# Schematic_v2.net
KiCad netlist of a schematic drawn in EAGLE
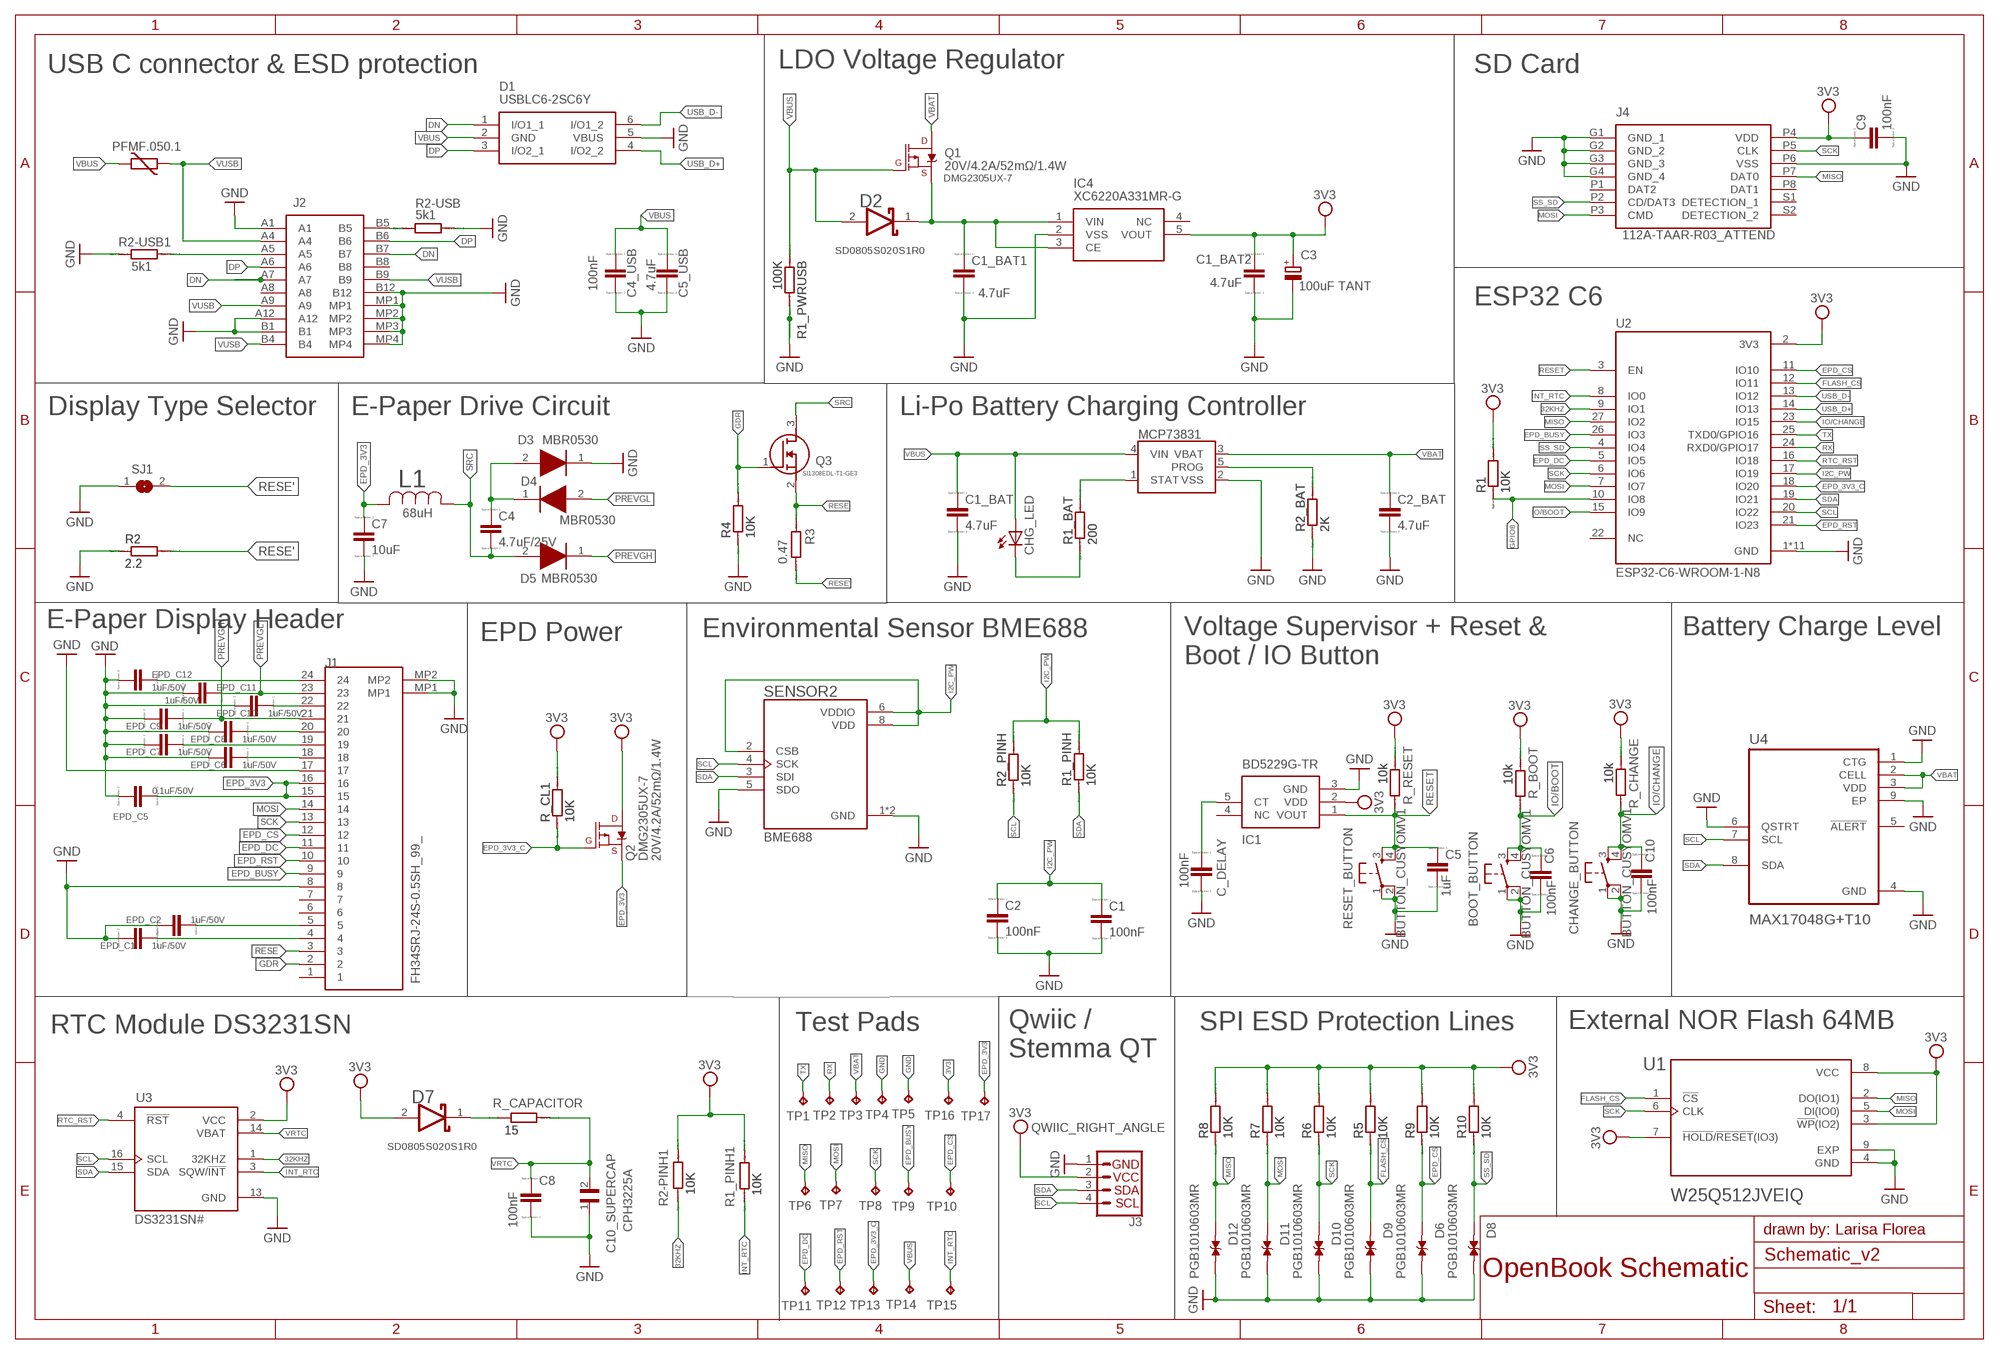
[diagram p0: schematic, sheet 1]

(export (version "E")
  (design (tool "Eeschema 10.0.6"))
  (components
    (comp (ref "BOOT_BUTTON")
      (value "BUTTON_CUSYOMV1")
      (footprint "eagle-import:MYBUTTON")
      (libsource (lib "eagle-import") (part "BUTTON_CUSYOMV1"))
    )
    (comp (ref "C1")
      (value "100nF")
      (footprint "eagle-import:EAGLE-LTSPICE_C0402")
      (libsource (lib "eagle-import") (part "EAGLE-LTSPICE_CC0402"))
    )
    (comp (ref "C1_BAT")
      (value "4.7uF")
      (footprint "eagle-import:EAGLE-LTSPICE_C0402")
      (libsource (lib "eagle-import") (part "EAGLE-LTSPICE_CC0402"))
    )
    (comp (ref "C1_BAT1")
      (value "4.7uF")
      (footprint "eagle-import:ESP32_WROVER_EAGLE-LTSPICE_C0402")
      (libsource (lib "eagle-import") (part "ESP32_WROVER_EAGLE-LTSPICE_CC0402"))
    )
    (comp (ref "C1_BAT2")
      (value "4.7uF")
      (footprint "eagle-import:ESP32_WROVER_EAGLE-LTSPICE_C0402")
      (libsource (lib "eagle-import") (part "ESP32_WROVER_EAGLE-LTSPICE_CC0402"))
    )
    (comp (ref "C2")
      (value "100nF")
      (footprint "eagle-import:EAGLE-LTSPICE_C0402")
      (libsource (lib "eagle-import") (part "EAGLE-LTSPICE_CC0402"))
    )
    (comp (ref "C2_BAT")
      (value "4.7uF")
      (footprint "eagle-import:EAGLE-LTSPICE_C0402")
      (libsource (lib "eagle-import") (part "EAGLE-LTSPICE_CC0402"))
    )
    (comp (ref "C3")
      (value "100uF TANT")
      (footprint "eagle-import:RCL_CT3528")
      (libsource (lib "eagle-import") (part "RCL_CPOL-EUCT3528"))
    )
    (comp (ref "C4")
      (value "4.7uF/25V")
      (footprint "eagle-import:ESP32_WROVER_EAGLE-LTSPICE_C0402")
      (libsource (lib "eagle-import") (part "ESP32_WROVER_EAGLE-LTSPICE_CC0402"))
    )
    (comp (ref "C4_USB")
      (value "100nF")
      (footprint "eagle-import:ESP32_WROVER_EAGLE-LTSPICE_C0402")
      (libsource (lib "eagle-import") (part "ESP32_WROVER_EAGLE-LTSPICE_CC0402"))
    )
    (comp (ref "C5")
      (value "1uF")
      (footprint "eagle-import:EAGLE-LTSPICE_C0402")
      (libsource (lib "eagle-import") (part "EAGLE-LTSPICE_CC0402"))
    )
    (comp (ref "C5_USB")
      (value "4.7uF")
      (footprint "eagle-import:ESP32_WROVER_EAGLE-LTSPICE_C0402")
      (libsource (lib "eagle-import") (part "ESP32_WROVER_EAGLE-LTSPICE_CC0402"))
    )
    (comp (ref "C6")
      (value "100nF")
      (footprint "eagle-import:EAGLE-LTSPICE_C0402")
      (libsource (lib "eagle-import") (part "EAGLE-LTSPICE_CC0402"))
    )
    (comp (ref "C7")
      (value "10uF")
      (footprint "eagle-import:ESP32_WROVER_EAGLE-LTSPICE_C0402")
      (libsource (lib "eagle-import") (part "ESP32_WROVER_EAGLE-LTSPICE_CC0402"))
    )
    (comp (ref "C8")
      (value "100nF")
      (footprint "eagle-import:EAGLE-LTSPICE_C0402")
      (libsource (lib "eagle-import") (part "EAGLE-LTSPICE_CC0402"))
    )
    (comp (ref "C9")
      (value "100nF")
      (footprint "eagle-import:EAGLE-LTSPICE_C0402")
      (libsource (lib "eagle-import") (part "EAGLE-LTSPICE_CC0402"))
    )
    (comp (ref "C10")
      (value "100nF")
      (footprint "eagle-import:EAGLE-LTSPICE_C0402")
      (libsource (lib "eagle-import") (part "EAGLE-LTSPICE_CC0402"))
    )
    (comp (ref "C10_SUPERCAP")
      (value "CPH3225A")
      (footprint "eagle-import:CAPCP3225X100N")
      (fields (field (name "MF") "Seiko Instruments"))
      (libsource (lib "eagle-import") (part "CPH3225A"))
    )
    (comp (ref "CHANGE_BUTTON")
      (value "BUTTON_CUSYOMV1")
      (footprint "eagle-import:MYBUTTON")
      (libsource (lib "eagle-import") (part "BUTTON_CUSYOMV1"))
    )
    (comp (ref "CHG_LED")
      (value "ADAFRUIT_LEDCHIP-LED0603")
      (footprint "eagle-import:ADAFRUIT_CHIP-LED0603")
      (libsource (lib "eagle-import") (part "ADAFRUIT_LEDCHIP-LED0603"))
    )
    (comp (ref "C_DELAY")
      (value "100nF")
      (footprint "eagle-import:EAGLE-LTSPICE_C0402")
      (libsource (lib "eagle-import") (part "EAGLE-LTSPICE_CC0402"))
    )
    (comp (ref "D1")
      (value "USBLC6-2SC6Y")
      (footprint "eagle-import:SOT95P280X145-6N")
      (fields (field (name "MF") "STMicroelectronics"))
      (libsource (lib "eagle-import") (part "USBLC6-2SC6Y"))
    )
    (comp (ref "D2")
      (value "ESP32_WROVER_AVX---SD0805S020S1R0_AVX_SD0805S020S1R0_0_0AVX_SD0805S020S1R0_0_0")
      (footprint "eagle-import:ESP32_WROVER_AVX---SD0805S020S1R0_AVX_SD0805S020S1R0_0")
      (fields
        (field (name "DIGIKEY_PART_NUMBER") "478-7800-1-ND")
        (field (name "MF") "AVX")
        (field (name "MOUSER_PART_NUMBER") "581-SD0805S020S1R0")
      )
      (libsource (lib "eagle-import") (part "ESP32_WROVER_AVX---SD0805S020S1R0_AVX_SD0805S020S1R0_0_0AVX_SD0805S020S1R0_0_0"))
    )
    (comp (ref "D3")
      (value "MBR0530")
      (footprint "eagle-import:SOD3716X135N")
      (fields (field (name "MF") "ON Semiconductor"))
      (libsource (lib "eagle-import") (part "MBR0530"))
    )
    (comp (ref "D4")
      (value "MBR0530")
      (footprint "eagle-import:SOD3716X135N")
      (fields (field (name "MF") "ON Semiconductor"))
      (libsource (lib "eagle-import") (part "MBR0530"))
    )
    (comp (ref "D5")
      (value "MBR0530")
      (footprint "eagle-import:SOD3716X135N")
      (fields (field (name "MF") "ON Semiconductor"))
      (libsource (lib "eagle-import") (part "MBR0530"))
    )
    (comp (ref "D6")
      (value "PGB1010603MR")
      (footprint "eagle-import:DIOC1608X36N")
      (fields (field (name "MF") "Littelfuse Inc."))
      (libsource (lib "eagle-import") (part "PGB1010603MR"))
    )
    (comp (ref "D7")
      (value "ESP32_WROVER_AVX---SD0805S020S1R0_AVX_SD0805S020S1R0_0_0AVX_SD0805S020S1R0_0_0")
      (footprint "eagle-import:ESP32_WROVER_AVX---SD0805S020S1R0_AVX_SD0805S020S1R0_0")
      (fields
        (field (name "DIGIKEY_PART_NUMBER") "478-7800-1-ND")
        (field (name "MF") "AVX")
        (field (name "MOUSER_PART_NUMBER") "581-SD0805S020S1R0")
      )
      (libsource (lib "eagle-import") (part "ESP32_WROVER_AVX---SD0805S020S1R0_AVX_SD0805S020S1R0_0_0AVX_SD0805S020S1R0_0_0"))
    )
    (comp (ref "D8")
      (value "PGB1010603MR")
      (footprint "eagle-import:DIOC1608X36N")
      (fields (field (name "MF") "Littelfuse Inc."))
      (libsource (lib "eagle-import") (part "PGB1010603MR"))
    )
    (comp (ref "D9")
      (value "PGB1010603MR")
      (footprint "eagle-import:DIOC1608X36N")
      (fields (field (name "MF") "Littelfuse Inc."))
      (libsource (lib "eagle-import") (part "PGB1010603MR"))
    )
    (comp (ref "D10")
      (value "PGB1010603MR")
      (footprint "eagle-import:DIOC1608X36N")
      (fields (field (name "MF") "Littelfuse Inc."))
      (libsource (lib "eagle-import") (part "PGB1010603MR"))
    )
    (comp (ref "D11")
      (value "PGB1010603MR")
      (footprint "eagle-import:DIOC1608X36N")
      (fields (field (name "MF") "Littelfuse Inc."))
      (libsource (lib "eagle-import") (part "PGB1010603MR"))
    )
    (comp (ref "D12")
      (value "PGB1010603MR")
      (footprint "eagle-import:DIOC1608X36N")
      (fields (field (name "MF") "Littelfuse Inc."))
      (libsource (lib "eagle-import") (part "PGB1010603MR"))
    )
    (comp (ref "EPD_C1")
      (value "1uF/50V")
      (footprint "eagle-import:ESP32_WROVER_EAGLE-LTSPICE_C0402")
      (libsource (lib "eagle-import") (part "DeskAssistant v19 v1_vf.GPlzlSHfQFaX3NeFr78fQQ_ESP32_WROVER_EAGLE-LTSPICE_CC0402"))
    )
    (comp (ref "EPD_C2")
      (value "1uF/50V")
      (footprint "eagle-import:ESP32_WROVER_EAGLE-LTSPICE_C0402")
      (libsource (lib "eagle-import") (part "DeskAssistant v19 v1_vf.GPlzlSHfQFaX3NeFr78fQQ_ESP32_WROVER_EAGLE-LTSPICE_CC0402"))
    )
    (comp (ref "EPD_C5")
      (value "0.1uF/50V")
      (footprint "eagle-import:ESP32_WROVER_EAGLE-LTSPICE_C0402")
      (libsource (lib "eagle-import") (part "DeskAssistant v19 v1_vf.GPlzlSHfQFaX3NeFr78fQQ_ESP32_WROVER_EAGLE-LTSPICE_CC0402"))
    )
    (comp (ref "EPD_C6")
      (value "1uF/50V")
      (footprint "eagle-import:ESP32_WROVER_EAGLE-LTSPICE_C0402")
      (libsource (lib "eagle-import") (part "DeskAssistant v19 v1_vf.GPlzlSHfQFaX3NeFr78fQQ_ESP32_WROVER_EAGLE-LTSPICE_CC0402"))
    )
    (comp (ref "EPD_C7")
      (value "1uF/50V")
      (footprint "eagle-import:ESP32_WROVER_EAGLE-LTSPICE_C0402")
      (libsource (lib "eagle-import") (part "DeskAssistant v19 v1_vf.GPlzlSHfQFaX3NeFr78fQQ_ESP32_WROVER_EAGLE-LTSPICE_CC0402"))
    )
    (comp (ref "EPD_C8")
      (value "1uF/50V")
      (footprint "eagle-import:ESP32_WROVER_EAGLE-LTSPICE_C0402")
      (libsource (lib "eagle-import") (part "DeskAssistant v19 v1_vf.GPlzlSHfQFaX3NeFr78fQQ_ESP32_WROVER_EAGLE-LTSPICE_CC0402"))
    )
    (comp (ref "EPD_C9")
      (value "1uF/50V")
      (footprint "eagle-import:ESP32_WROVER_EAGLE-LTSPICE_C0402")
      (libsource (lib "eagle-import") (part "DeskAssistant v19 v1_vf.GPlzlSHfQFaX3NeFr78fQQ_ESP32_WROVER_EAGLE-LTSPICE_CC0402"))
    )
    (comp (ref "EPD_C10")
      (value "1uF/50V")
      (footprint "eagle-import:ESP32_WROVER_EAGLE-LTSPICE_C0402")
      (libsource (lib "eagle-import") (part "DeskAssistant v19 v1_vf.GPlzlSHfQFaX3NeFr78fQQ_ESP32_WROVER_EAGLE-LTSPICE_CC0402"))
    )
    (comp (ref "EPD_C11")
      (value "1uF/50V")
      (footprint "eagle-import:ESP32_WROVER_EAGLE-LTSPICE_C0402")
      (libsource (lib "eagle-import") (part "DeskAssistant v19 v1_vf.GPlzlSHfQFaX3NeFr78fQQ_ESP32_WROVER_EAGLE-LTSPICE_CC0402"))
    )
    (comp (ref "EPD_C12")
      (value "1uF/50V")
      (footprint "eagle-import:ESP32_WROVER_EAGLE-LTSPICE_C0402")
      (libsource (lib "eagle-import") (part "DeskAssistant v19 v1_vf.GPlzlSHfQFaX3NeFr78fQQ_ESP32_WROVER_EAGLE-LTSPICE_CC0402"))
    )
    (comp (ref "IC1")
      (value "BD5229G-TR")
      (footprint "eagle-import:SOT95P280X125-5N")
      (fields (field (name "MOUSER_PART_NUMBER") "755-BD5229G-TR"))
      (libsource (lib "eagle-import") (part "BD5229G-TR"))
    )
    (comp (ref "IC4")
      (value "XC6220A331MR-G")
      (footprint "eagle-import:SOT95P280X120-5N")
      (fields (field (name "MOUSER_PART_NUMBER") "865-XC6220A331MR-G"))
      (libsource (lib "eagle-import") (part "XC6220A331MR-G"))
    )
    (comp (ref "J1")
      (value "FH34SRJ-24S-0.5SH_99_")
      (footprint "eagle-import:FH34SRJ24S05SH99")
      (fields
        (field (name "MANUFACTURER_PART_NUMBER") "FH34SRJ-24S-0.5SH(99)")
        (field (name "MOUSER_PART_NUMBER") "798-FH34SRJ24S05SH99")
      )
      (libsource (lib "eagle-import") (part "FH34SRJ-24S-0.5SH_99_"))
    )
    (comp (ref "J2")
      (value "SAMACSYS_PARTS_USB4110-GF-A")
      (footprint "eagle-import:SAMACSYS_PARTS_USB4110GFA")
      (fields
        (field (name "MANUFACTURER_PART_NUMBER") "USB4110-GF-A")
        (field (name "MOUSER_PART_NUMBER") "640-USB4110-GF-A")
      )
      (libsource (lib "eagle-import") (part "SAMACSYS_PARTS_USB4110-GF-A"))
    )
    (comp (ref "J3")
      (value "QWIIC_RIGHT_ANGLE")
      (footprint "eagle-import:JST04_1MM_RA")
      (libsource (lib "eagle-import") (part "QWIIC_CONNECTORJS-1MM"))
    )
    (comp (ref "J4")
      (value "112A-TAAR-R03_ATTEND")
      (footprint "eagle-import:112ATAARR03ATTEND")
      (fields (field (name "MANUFACTURER_PART_NUMBER") "112A-TAAR-R03 ATTEND"))
      (libsource (lib "eagle-import") (part "112A-TAAR-R03_ATTEND"))
    )
    (comp (ref "L1")
      (value "744043680IND_4828-WE-TPC_WRE")
      (footprint "eagle-import:IND_4828-WE-TPC_WRE")
      (fields
        (field (name "MANUFACTURER_PART_NUMBER") "744043680")
        (field (name "68UH") "68uH")
        (field (name "COPYRIGHT") "Copyright (C) 2024 Ultra Librarian. All rights reserved.")
      )
      (libsource (lib "eagle-import") (part "744043680IND_4828-WE-TPC_WRE"))
    )
    (comp (ref "MCP73831")
      (value "ESP32_WROVER_SPARKFUN-IC-POWER_MCP73831")
      (footprint "eagle-import:ESP32_WROVER_SPARKFUN-IC-POWER_SOT23-5")
      (libsource (lib "eagle-import") (part "ESP32_WROVER_SPARKFUN-IC-POWER_MCP73831"))
    )
    (comp (ref "PFMF.050.1")
      (value "ESP32C6_VARISTORCN1812")
      (footprint "eagle-import:ESP32C6_VARISTOR_CT_CN1812")
      (libsource (lib "eagle-import") (part "ESP32C6_VARISTORCN1812"))
    )
    (comp (ref "Q1")
      (value "20V/4.2A/52mΩ/1.4W")
      (footprint "eagle-import:ESP32_WROVER_SPARKFUN-DISCRETESEMI_SOT23-3")
      (libsource (lib "eagle-import") (part "ESP32_WROVER_SPARKFUN-DISCRETESEMI_MOSFET_PCH-DMG2305UX-7"))
    )
    (comp (ref "Q2")
      (value "20V/4.2A/52mΩ/1.4W")
      (footprint "eagle-import:ESP32_WROVER_SPARKFUN-DISCRETESEMI_SOT23-3")
      (libsource (lib "eagle-import") (part "ESP32_WROVER_SPARKFUN-DISCRETESEMI_MOSFET_PCH-DMG2305UX-7"))
    )
    (comp (ref "Q3")
      (value "SI1308EDL-T1-GE3")
      (footprint "eagle-import:SOT65P210X110-3N")
      (fields (field (name "MF") "Vishay Siliconix"))
      (libsource (lib "eagle-import") (part "SI1308EDL-T1-GE3"))
    )
    (comp (ref "R1")
      (value "10K")
      (footprint "eagle-import:ESP32_WROVER_EAGLE-LTSPICE_R0402")
      (libsource (lib "eagle-import") (part "ESP32_WROVER_EAGLE-LTSPICE_RR0402"))
    )
    (comp (ref "R1_BAT")
      (value "200")
      (footprint "eagle-import:ESP32_WROVER_EAGLE-LTSPICE_R0402")
      (libsource (lib "eagle-import") (part "ESP32_WROVER_EAGLE-LTSPICE_RR0402"))
    )
    (comp (ref "R1_PINH")
      (value "10K")
      (footprint "eagle-import:ESP32_WROVER_EAGLE-LTSPICE_R0402")
      (libsource (lib "eagle-import") (part "ESP32_WROVER_EAGLE-LTSPICE_RR0402"))
    )
    (comp (ref "R1_PINH1")
      (value "10K")
      (footprint "eagle-import:ESP32_WROVER_EAGLE-LTSPICE_R0402")
      (libsource (lib "eagle-import") (part "ESP32_WROVER_EAGLE-LTSPICE_RR0402"))
    )
    (comp (ref "R1_PWRUSB")
      (value "100K")
      (footprint "eagle-import:ESP32_WROVER_EAGLE-LTSPICE_R0402")
      (libsource (lib "eagle-import") (part "ESP32_WROVER_EAGLE-LTSPICE_RR0402"))
    )
    (comp (ref "R2")
      (value "2.2")
      (footprint "eagle-import:ESP32_WROVER_EAGLE-LTSPICE_R0402")
      (libsource (lib "eagle-import") (part "ESP32_WROVER_EAGLE-LTSPICE_RR0402"))
    )
    (comp (ref "R2-PINH1")
      (value "10K")
      (footprint "eagle-import:ESP32_WROVER_EAGLE-LTSPICE_R0402")
      (libsource (lib "eagle-import") (part "ESP32_WROVER_EAGLE-LTSPICE_RR0402"))
    )
    (comp (ref "R2-USB")
      (value "5k1")
      (footprint "eagle-import:ESP32_WROVER_EAGLE-LTSPICE_R0402")
      (libsource (lib "eagle-import") (part "ESP32_WROVER_EAGLE-LTSPICE_RR0402"))
    )
    (comp (ref "R2-USB1")
      (value "5k1")
      (footprint "eagle-import:ESP32_WROVER_EAGLE-LTSPICE_R0402")
      (libsource (lib "eagle-import") (part "ESP32_WROVER_EAGLE-LTSPICE_RR0402"))
    )
    (comp (ref "R2_BAT")
      (value "2K")
      (footprint "eagle-import:ESP32_WROVER_EAGLE-LTSPICE_R0402")
      (libsource (lib "eagle-import") (part "ESP32_WROVER_EAGLE-LTSPICE_RR0402"))
    )
    (comp (ref "R2_PINH")
      (value "10K")
      (footprint "eagle-import:ESP32_WROVER_EAGLE-LTSPICE_R0402")
      (libsource (lib "eagle-import") (part "ESP32_WROVER_EAGLE-LTSPICE_RR0402"))
    )
    (comp (ref "R3")
      (value "0.47")
      (footprint "eagle-import:ESP32_WROVER_EAGLE-LTSPICE_R0402")
      (libsource (lib "eagle-import") (part "ESP32_WROVER_EAGLE-LTSPICE_RR0402"))
    )
    (comp (ref "R4")
      (value "10K")
      (footprint "eagle-import:ESP32_WROVER_EAGLE-LTSPICE_R0402")
      (libsource (lib "eagle-import") (part "ESP32_WROVER_EAGLE-LTSPICE_RR0402"))
    )
    (comp (ref "R5")
      (value "10K")
      (footprint "eagle-import:ESP32_WROVER_EAGLE-LTSPICE_R0402")
      (libsource (lib "eagle-import") (part "DeskAssistant v19 v1_vf.GPlzlSHfQFaX3NeFr78fQQ_ESP32_WROVER_EAGLE-LTSPICE_RR0402"))
    )
    (comp (ref "R6")
      (value "10K")
      (footprint "eagle-import:ESP32_WROVER_EAGLE-LTSPICE_R0402")
      (libsource (lib "eagle-import") (part "DeskAssistant v19 v1_vf.GPlzlSHfQFaX3NeFr78fQQ_ESP32_WROVER_EAGLE-LTSPICE_RR0402"))
    )
    (comp (ref "R7")
      (value "10K")
      (footprint "eagle-import:ESP32_WROVER_EAGLE-LTSPICE_R0402")
      (libsource (lib "eagle-import") (part "DeskAssistant v19 v1_vf.GPlzlSHfQFaX3NeFr78fQQ_ESP32_WROVER_EAGLE-LTSPICE_RR0402"))
    )
    (comp (ref "R8")
      (value "10K")
      (footprint "eagle-import:ESP32_WROVER_EAGLE-LTSPICE_R0402")
      (libsource (lib "eagle-import") (part "DeskAssistant v19 v1_vf.GPlzlSHfQFaX3NeFr78fQQ_ESP32_WROVER_EAGLE-LTSPICE_RR0402"))
    )
    (comp (ref "R9")
      (value "10K")
      (footprint "eagle-import:ESP32_WROVER_EAGLE-LTSPICE_R0402")
      (libsource (lib "eagle-import") (part "DeskAssistant v19 v1_vf.GPlzlSHfQFaX3NeFr78fQQ_ESP32_WROVER_EAGLE-LTSPICE_RR0402"))
    )
    (comp (ref "R10")
      (value "10K")
      (footprint "eagle-import:ESP32_WROVER_EAGLE-LTSPICE_R0402")
      (libsource (lib "eagle-import") (part "DeskAssistant v19 v1_vf.GPlzlSHfQFaX3NeFr78fQQ_ESP32_WROVER_EAGLE-LTSPICE_RR0402"))
    )
    (comp (ref "RESET_BUTTON")
      (value "BUTTON_CUSYOMV1")
      (footprint "eagle-import:MYBUTTON")
      (libsource (lib "eagle-import") (part "BUTTON_CUSYOMV1"))
    )
    (comp (ref "R_BOOT")
      (value "10k")
      (footprint "eagle-import:ESP32_WROVER_EAGLE-LTSPICE_R0402")
      (libsource (lib "eagle-import") (part "ESP32_WROVER_EAGLE-LTSPICE_RR0402"))
    )
    (comp (ref "R_CAPACITOR")
      (value "15")
      (footprint "eagle-import:ESP32_WROVER_EAGLE-LTSPICE_R0402")
      (libsource (lib "eagle-import") (part "ESP32_WROVER_EAGLE-LTSPICE_RR0402"))
    )
    (comp (ref "R_CHANGE")
      (value "10k")
      (footprint "eagle-import:ESP32_WROVER_EAGLE-LTSPICE_R0402")
      (libsource (lib "eagle-import") (part "ESP32_WROVER_EAGLE-LTSPICE_RR0402"))
    )
    (comp (ref "R_CL1")
      (value "10K")
      (footprint "eagle-import:ESP32_WROVER_EAGLE-LTSPICE_R0402")
      (libsource (lib "eagle-import") (part "ESP32_WROVER_EAGLE-LTSPICE_RR0402"))
    )
    (comp (ref "R_RESET")
      (value "10k")
      (footprint "eagle-import:ESP32_WROVER_EAGLE-LTSPICE_R0402")
      (libsource (lib "eagle-import") (part "ESP32_WROVER_EAGLE-LTSPICE_RR0402"))
    )
    (comp (ref "SENSOR2")
      (value "ESP32_WROVER_BME680_BME680")
      (footprint "eagle-import:ESP32_WROVER_BME680_PSON80P300X300X100-8N")
      (fields (field (name "MF") "Bosch Sensortec") (field (name "MP") "BME680"))
      (libsource (lib "eagle-import") (part "ESP32_WROVER_BME680_BME680"))
    )
    (comp (ref "SJ1") (value "SJ") (footprint "eagle-import:SJ") (libsource (lib "eagle-import") (part "SJ")))
    (comp (ref "TP1")
      (value "TPTP20R")
      (footprint "eagle-import:TP20R")
      (libsource (lib "eagle-import") (part "TPTP20R"))
    )
    (comp (ref "TP2")
      (value "TPTP20R")
      (footprint "eagle-import:TP20R")
      (libsource (lib "eagle-import") (part "TPTP20R"))
    )
    (comp (ref "TP3")
      (value "TPTP20R")
      (footprint "eagle-import:TP20R")
      (libsource (lib "eagle-import") (part "TPTP20R"))
    )
    (comp (ref "TP4")
      (value "TPTP20R")
      (footprint "eagle-import:TP20R")
      (libsource (lib "eagle-import") (part "TPTP20R"))
    )
    (comp (ref "TP5")
      (value "TPTP20R")
      (footprint "eagle-import:TP20R")
      (libsource (lib "eagle-import") (part "TPTP20R"))
    )
    (comp (ref "TP6")
      (value "TPTP20R")
      (footprint "eagle-import:TP20R")
      (libsource (lib "eagle-import") (part "TPTP20R"))
    )
    (comp (ref "TP7")
      (value "TPTP20R")
      (footprint "eagle-import:TP20R")
      (libsource (lib "eagle-import") (part "TPTP20R"))
    )
    (comp (ref "TP8")
      (value "TPTP20R")
      (footprint "eagle-import:TP20R")
      (libsource (lib "eagle-import") (part "TPTP20R"))
    )
    (comp (ref "TP9")
      (value "TPTP20R")
      (footprint "eagle-import:TP20R")
      (libsource (lib "eagle-import") (part "TPTP20R"))
    )
    (comp (ref "TP10")
      (value "TPTP20R")
      (footprint "eagle-import:TP20R")
      (libsource (lib "eagle-import") (part "TPTP20R"))
    )
    (comp (ref "TP11")
      (value "TPTP20R")
      (footprint "eagle-import:TP20R")
      (libsource (lib "eagle-import") (part "TPTP20R"))
    )
    (comp (ref "TP12")
      (value "TPTP20R")
      (footprint "eagle-import:TP20R")
      (libsource (lib "eagle-import") (part "TPTP20R"))
    )
    (comp (ref "TP13")
      (value "TPTP20R")
      (footprint "eagle-import:TP20R")
      (libsource (lib "eagle-import") (part "TPTP20R"))
    )
    (comp (ref "TP14")
      (value "TPTP20R")
      (footprint "eagle-import:TP20R")
      (libsource (lib "eagle-import") (part "TPTP20R"))
    )
    (comp (ref "TP15")
      (value "TPTP20R")
      (footprint "eagle-import:TP20R")
      (libsource (lib "eagle-import") (part "TPTP20R"))
    )
    (comp (ref "TP16")
      (value "TPTP20R")
      (footprint "eagle-import:TP20R")
      (libsource (lib "eagle-import") (part "TPTP20R"))
    )
    (comp (ref "TP17")
      (value "TPTP20R")
      (footprint "eagle-import:TP20R")
      (libsource (lib "eagle-import") (part "TPTP20R"))
    )
    (comp (ref "U1")
      (value "W25Q512JVEIQ")
      (footprint "eagle-import:SON127P600X800X80-9N")
      (fields (field (name "MF") "Winbond Electronics"))
      (libsource (lib "eagle-import") (part "W25Q512JVEIQ"))
    )
    (comp (ref "U2")
      (value "ESP32-C6-WROOM-1-N8")
      (footprint "eagle-import:XCVR_ESP32-C6-WROOM-1-N8")
      (fields (field (name "MF") "Espressif Systems"))
      (libsource (lib "eagle-import") (part "ESP32-C6-WROOM-1-N8"))
    )
    (comp (ref "U3")
      (value "DS3231SN#")
      (footprint "eagle-import:SOIC127P1032X265-16N")
      (fields (field (name "MF") "Analog Devices"))
      (libsource (lib "eagle-import") (part "DS3231SN#"))
    )
    (comp (ref "U4")
      (value "MAX17048G+T10")
      (footprint "eagle-import:SON50P200X200X80-9N")
      (fields (field (name "MF") "Analog Devices"))
      (libsource (lib "eagle-import") (part "MAX17048G+T10"))
    )
  )
  (nets
    (net (code "1") (name "3V3") (class "Default")
      (node (ref "C1_BAT2") (pin "1") (pinfunction "1_1") (pintype "passive"))
      (node (ref "C3") (pin "+") (pinfunction "+_+") (pintype "passive"))
      (node (ref "C9") (pin "1") (pinfunction "1_1") (pintype "passive"))
      (node (ref "D7") (pin "2") (pinfunction "ANODE_2") (pintype "bidirectional"))
      (node (ref "IC1") (pin "2") (pinfunction "VDD_2") (pintype "bidirectional"))
      (node (ref "IC4") (pin "5") (pinfunction "VOUT_5") (pintype "bidirectional"))
      (node (ref "J3") (pin "2") (pinfunction "2_2") (pintype "power_in"))
      (node (ref "J4") (pin "P4") (pinfunction "VDD_P4") (pintype "bidirectional"))
      (node (ref "Q2") (pin "3") (pinfunction "D_3") (pintype "bidirectional"))
      (node (ref "R1") (pin "2") (pinfunction "2_2") (pintype "passive"))
      (node (ref "R10") (pin "2") (pinfunction "2_2") (pintype "passive"))
      (node (ref "R1_PINH1") (pin "2") (pinfunction "2_2") (pintype "passive"))
      (node (ref "R2-PINH1") (pin "2") (pinfunction "2_2") (pintype "passive"))
      (node (ref "R5") (pin "2") (pinfunction "2_2") (pintype "passive"))
      (node (ref "R6") (pin "2") (pinfunction "2_2") (pintype "passive"))
      (node (ref "R7") (pin "2") (pinfunction "2_2") (pintype "passive"))
      (node (ref "R8") (pin "2") (pinfunction "2_2") (pintype "passive"))
      (node (ref "R9") (pin "2") (pinfunction "2_2") (pintype "passive"))
      (node (ref "R_BOOT") (pin "1") (pinfunction "1_1") (pintype "passive"))
      (node (ref "R_CHANGE") (pin "1") (pinfunction "1_1") (pintype "passive"))
      (node (ref "R_CL1") (pin "2") (pinfunction "2_2") (pintype "passive"))
      (node (ref "R_RESET") (pin "1") (pinfunction "1_1") (pintype "passive"))
      (node (ref "TP16") (pin "TP") (pinfunction "TP_TP") (pintype "input"))
      (node (ref "U1") (pin "3") (pinfunction "~{WP}(IO2)_3") (pintype "bidirectional"))
      (node (ref "U1") (pin "7") (pinfunction "~{HOLD}/~{RESET}(IO3)_7") (pintype "bidirectional"))
      (node (ref "U1") (pin "8") (pinfunction "VCC_8") (pintype "power_in"))
      (node (ref "U2") (pin "2") (pinfunction "3V3_2") (pintype "power_in"))
      (node (ref "U3") (pin "2") (pinfunction "VCC_2") (pintype "power_in"))
    )
    (net (code "2") (name "32KHZ") (class "Default")
      (node (ref "R2-PINH1") (pin "1") (pinfunction "1_1") (pintype "passive"))
      (node (ref "U2") (pin "9") (pinfunction "IO1_9") (pintype "bidirectional"))
      (node (ref "U3") (pin "1") (pinfunction "32KHZ_1") (pintype "output"))
    )
    (net (code "3") (name "DN") (class "Default")
      (node (ref "D1") (pin "1") (pinfunction "I/O1_1_1") (pintype "bidirectional"))
      (node (ref "J2") (pin "A7") (pinfunction "A7_A7") (pintype "bidirectional"))
      (node (ref "J2") (pin "B7") (pinfunction "B7_B7") (pintype "bidirectional"))
    )
    (net (code "4") (name "DP") (class "Default")
      (node (ref "D1") (pin "3") (pinfunction "I/O2_1_3") (pintype "bidirectional"))
      (node (ref "J2") (pin "A6") (pinfunction "A6_A6") (pintype "bidirectional"))
      (node (ref "J2") (pin "B6") (pinfunction "B6_B6") (pintype "bidirectional"))
    )
    (net (code "5") (name "EPD_3V3") (class "Default")
      (node (ref "C7") (pin "1") (pinfunction "1_1") (pintype "passive"))
      (node (ref "EPD_C5") (pin "1") (pinfunction "1_1") (pintype "passive"))
      (node (ref "J1") (pin "15") (pinfunction "15_15") (pintype "bidirectional"))
      (node (ref "J1") (pin "16") (pinfunction "16_16") (pintype "bidirectional"))
      (node (ref "L1") (pin "2") (pinfunction "2_2") (pintype "passive"))
      (node (ref "Q2") (pin "2") (pinfunction "S_2") (pintype "bidirectional"))
      (node (ref "TP17") (pin "TP") (pinfunction "TP_TP") (pintype "input"))
    )
    (net (code "6") (name "EPD_3V3_C") (class "Default")
      (node (ref "Q2") (pin "1") (pinfunction "G_1") (pintype "bidirectional"))
      (node (ref "R_CL1") (pin "1") (pinfunction "1_1") (pintype "passive"))
      (node (ref "TP13") (pin "TP") (pinfunction "TP_TP") (pintype "input"))
      (node (ref "U2") (pin "18") (pinfunction "IO20_18") (pintype "bidirectional"))
    )
    (net (code "7") (name "EPD_BUSY") (class "Default")
      (node (ref "J1") (pin "9") (pinfunction "9_9") (pintype "bidirectional"))
      (node (ref "TP9") (pin "TP") (pinfunction "TP_TP") (pintype "input"))
      (node (ref "U2") (pin "26") (pinfunction "IO3_26") (pintype "bidirectional"))
    )
    (net (code "8") (name "EPD_CS") (class "Default")
      (node (ref "D6") (pin "1") (pinfunction "1_1") (pintype "passive"))
      (node (ref "J1") (pin "12") (pinfunction "12_12") (pintype "bidirectional"))
      (node (ref "R9") (pin "1") (pinfunction "1_1") (pintype "passive"))
      (node (ref "TP10") (pin "TP") (pinfunction "TP_TP") (pintype "input"))
      (node (ref "U2") (pin "11") (pinfunction "IO10_11") (pintype "bidirectional"))
    )
    (net (code "9") (name "EPD_DC") (class "Default")
      (node (ref "J1") (pin "11") (pinfunction "11_11") (pintype "bidirectional"))
      (node (ref "TP11") (pin "TP") (pinfunction "TP_TP") (pintype "input"))
      (node (ref "U2") (pin "5") (pinfunction "IO5_5") (pintype "bidirectional"))
    )
    (net (code "10") (name "EPD_RST") (class "Default")
      (node (ref "J1") (pin "10") (pinfunction "10_10") (pintype "bidirectional"))
      (node (ref "TP12") (pin "TP") (pinfunction "TP_TP") (pintype "input"))
      (node (ref "U2") (pin "21") (pinfunction "IO23_21") (pintype "bidirectional"))
    )
    (net (code "11") (name "FLASH_CS") (class "Default")
      (node (ref "D9") (pin "1") (pinfunction "1_1") (pintype "passive"))
      (node (ref "R5") (pin "1") (pinfunction "1_1") (pintype "passive"))
      (node (ref "U1") (pin "1") (pinfunction "~{CS}_1") (pintype "input"))
      (node (ref "U2") (pin "12") (pinfunction "IO11_12") (pintype "bidirectional"))
    )
    (net (code "12") (name "GDR") (class "Default")
      (node (ref "J1") (pin "2") (pinfunction "2_2") (pintype "bidirectional"))
      (node (ref "Q3") (pin "1") (pinfunction "G_1") (pintype "bidirectional"))
      (node (ref "R4") (pin "2") (pinfunction "2_2") (pintype "passive"))
    )
    (net (code "13") (name "GND") (class "Default")
      (node (ref "BOOT_BUTTON") (pin "1") (pinfunction "1_1") (pintype "passive"))
      (node (ref "BOOT_BUTTON") (pin "2") (pinfunction "2_2") (pintype "passive"))
      (node (ref "C1") (pin "2") (pinfunction "2_2") (pintype "passive"))
      (node (ref "C10") (pin "2") (pinfunction "2_2") (pintype "passive"))
      (node (ref "C10_SUPERCAP") (pin "1") (pinfunction "1_1") (pintype "passive"))
      (node (ref "C1_BAT") (pin "2") (pinfunction "2_2") (pintype "passive"))
      (node (ref "C1_BAT1") (pin "2") (pinfunction "2_2") (pintype "passive"))
      (node (ref "C1_BAT2") (pin "2") (pinfunction "2_2") (pintype "passive"))
      (node (ref "C2") (pin "2") (pinfunction "2_2") (pintype "passive"))
      (node (ref "C2_BAT") (pin "2") (pinfunction "2_2") (pintype "passive"))
      (node (ref "C3") (pin "-") (pinfunction "-_-") (pintype "passive"))
      (node (ref "C4_USB") (pin "2") (pinfunction "2_2") (pintype "passive"))
      (node (ref "C5") (pin "2") (pinfunction "2_2") (pintype "passive"))
      (node (ref "C5_USB") (pin "2") (pinfunction "2_2") (pintype "passive"))
      (node (ref "C6") (pin "2") (pinfunction "2_2") (pintype "passive"))
      (node (ref "C7") (pin "2") (pinfunction "2_2") (pintype "passive"))
      (node (ref "C8") (pin "2") (pinfunction "2_2") (pintype "passive"))
      (node (ref "C9") (pin "2") (pinfunction "2_2") (pintype "passive"))
      (node (ref "CHANGE_BUTTON") (pin "1") (pinfunction "1_1") (pintype "passive"))
      (node (ref "CHANGE_BUTTON") (pin "2") (pinfunction "2_2") (pintype "passive"))
      (node (ref "C_DELAY") (pin "2") (pinfunction "2_2") (pintype "passive"))
      (node (ref "D1") (pin "5") (pinfunction "VBUS_5") (pintype "bidirectional"))
      (node (ref "D10") (pin "2") (pinfunction "2_2") (pintype "passive"))
      (node (ref "D11") (pin "2") (pinfunction "2_2") (pintype "passive"))
      (node (ref "D12") (pin "2") (pinfunction "2_2") (pintype "passive"))
      (node (ref "D3") (pin "1") (pinfunction "K_1") (pintype "bidirectional"))
      (node (ref "D6") (pin "2") (pinfunction "2_2") (pintype "passive"))
      (node (ref "D8") (pin "2") (pinfunction "2_2") (pintype "passive"))
      (node (ref "D9") (pin "2") (pinfunction "2_2") (pintype "passive"))
      (node (ref "EPD_C1") (pin "2") (pinfunction "2_2") (pintype "passive"))
      (node (ref "EPD_C10") (pin "2") (pinfunction "2_2") (pintype "passive"))
      (node (ref "EPD_C11") (pin "2") (pinfunction "2_2") (pintype "passive"))
      (node (ref "EPD_C12") (pin "2") (pinfunction "2_2") (pintype "passive"))
      (node (ref "EPD_C2") (pin "2") (pinfunction "2_2") (pintype "passive"))
      (node (ref "EPD_C5") (pin "2") (pinfunction "2_2") (pintype "passive"))
      (node (ref "EPD_C6") (pin "2") (pinfunction "2_2") (pintype "passive"))
      (node (ref "EPD_C7") (pin "2") (pinfunction "2_2") (pintype "passive"))
      (node (ref "EPD_C8") (pin "2") (pinfunction "2_2") (pintype "passive"))
      (node (ref "EPD_C9") (pin "2") (pinfunction "2_2") (pintype "passive"))
      (node (ref "IC1") (pin "3") (pinfunction "GND_3") (pintype "bidirectional"))
      (node (ref "IC4") (pin "2") (pinfunction "VSS_2") (pintype "bidirectional"))
      (node (ref "J1") (pin "17") (pinfunction "17_17") (pintype "bidirectional"))
      (node (ref "J1") (pin "8") (pinfunction "8_8") (pintype "bidirectional"))
      (node (ref "J1") (pin "MP1") (pinfunction "MP1_MP1") (pintype "bidirectional"))
      (node (ref "J1") (pin "MP2") (pinfunction "MP2_MP2") (pintype "bidirectional"))
      (node (ref "J2") (pin "A1") (pinfunction "A1_A1") (pintype "bidirectional"))
      (node (ref "J2") (pin "A12") (pinfunction "A12_A12") (pintype "bidirectional"))
      (node (ref "J2") (pin "B1") (pinfunction "B1_B1") (pintype "bidirectional"))
      (node (ref "J2") (pin "B12") (pinfunction "B12_B12") (pintype "bidirectional"))
      (node (ref "J2") (pin "MP1") (pinfunction "MP1_MP1") (pintype "bidirectional"))
      (node (ref "J2") (pin "MP2") (pinfunction "MP2_MP2") (pintype "bidirectional"))
      (node (ref "J2") (pin "MP3") (pinfunction "MP3_MP3") (pintype "bidirectional"))
      (node (ref "J2") (pin "MP4") (pinfunction "MP4_MP4") (pintype "bidirectional"))
      (node (ref "J3") (pin "1") (pinfunction "1_1") (pintype "power_in"))
      (node (ref "J4") (pin "G1") (pinfunction "GND_1_G1") (pintype "bidirectional"))
      (node (ref "J4") (pin "G2") (pinfunction "GND_2_G2") (pintype "bidirectional"))
      (node (ref "J4") (pin "G3") (pinfunction "GND_3_G3") (pintype "bidirectional"))
      (node (ref "J4") (pin "G4") (pinfunction "GND_4_G4") (pintype "bidirectional"))
      (node (ref "J4") (pin "P6") (pinfunction "VSS_P6") (pintype "bidirectional"))
      (node (ref "MCP73831") (pin "2") (pinfunction "VSS_2") (pintype "power_in"))
      (node (ref "R1_PWRUSB") (pin "2") (pinfunction "2_2") (pintype "passive"))
      (node (ref "R2") (pin "1") (pinfunction "1_1") (pintype "passive"))
      (node (ref "R2-USB") (pin "2") (pinfunction "2_2") (pintype "passive"))
      (node (ref "R2-USB1") (pin "1") (pinfunction "1_1") (pintype "passive"))
      (node (ref "R2_BAT") (pin "1") (pinfunction "1_1") (pintype "passive"))
      (node (ref "R4") (pin "1") (pinfunction "1_1") (pintype "passive"))
      (node (ref "RESET_BUTTON") (pin "1") (pinfunction "1_1") (pintype "passive"))
      (node (ref "RESET_BUTTON") (pin "2") (pinfunction "2_2") (pintype "passive"))
      (node (ref "SENSOR2") (pin "1") (pinfunction "GND_1") (pintype "power_in"))
      (node (ref "SENSOR2") (pin "5") (pinfunction "SDO_5") (pintype "bidirectional"))
      (node (ref "SENSOR2") (pin "7") (pinfunction "GND_7") (pintype "power_in"))
      (node (ref "SJ1") (pin "1") (pinfunction "1_1") (pintype "passive"))
      (node (ref "TP4") (pin "TP") (pinfunction "TP_TP") (pintype "input"))
      (node (ref "TP5") (pin "TP") (pinfunction "TP_TP") (pintype "input"))
      (node (ref "U1") (pin "4") (pinfunction "GND_4") (pintype "power_in"))
      (node (ref "U1") (pin "9") (pinfunction "EXP_9") (pintype "passive"))
      (node (ref "U2") (pin "1") (pinfunction "GND_1") (pintype "power_in"))
      (node (ref "U2") (pin "28") (pinfunction "GND_28") (pintype "power_in"))
      (node (ref "U2") (pin "29_1") (pinfunction "GND_29_1") (pintype "power_in"))
      (node (ref "U2") (pin "29_2") (pinfunction "GND_29_2") (pintype "power_in"))
      (node (ref "U2") (pin "29_3") (pinfunction "GND_29_3") (pintype "power_in"))
      (node (ref "U2") (pin "29_4") (pinfunction "GND_29_4") (pintype "power_in"))
      (node (ref "U2") (pin "29_5") (pinfunction "GND_29_5") (pintype "power_in"))
      (node (ref "U2") (pin "29_6") (pinfunction "GND_29_6") (pintype "power_in"))
      (node (ref "U2") (pin "29_7") (pinfunction "GND_29_7") (pintype "power_in"))
      (node (ref "U2") (pin "29_8") (pinfunction "GND_29_8") (pintype "power_in"))
      (node (ref "U2") (pin "29_9") (pinfunction "GND_29_9") (pintype "power_in"))
      (node (ref "U3") (pin "13") (pinfunction "GND_13") (pintype "power_in"))
      (node (ref "U4") (pin "1") (pinfunction "CTG_1") (pintype "power_in"))
      (node (ref "U4") (pin "4") (pinfunction "GND_4") (pintype "power_in"))
      (node (ref "U4") (pin "6") (pinfunction "QSTRT_6") (pintype "input"))
      (node (ref "U4") (pin "9") (pinfunction "EP_9") (pintype "power_in"))
    )
    (net (code "14") (name "GPIO8") (class "Default")
      (node (ref "R1") (pin "1") (pinfunction "1_1") (pintype "passive"))
      (node (ref "U2") (pin "10") (pinfunction "IO8_10") (pintype "bidirectional"))
    )
    (net (code "15") (name "I2C_PW") (class "Default")
      (node (ref "C1") (pin "1") (pinfunction "1_1") (pintype "passive"))
      (node (ref "C2") (pin "1") (pinfunction "1_1") (pintype "passive"))
      (node (ref "R1_PINH") (pin "2") (pinfunction "2_2") (pintype "passive"))
      (node (ref "R2_PINH") (pin "2") (pinfunction "2_2") (pintype "passive"))
      (node (ref "SENSOR2") (pin "2") (pinfunction "CSB_2") (pintype "input"))
      (node (ref "SENSOR2") (pin "6") (pinfunction "VDDIO_6") (pintype "power_in"))
      (node (ref "SENSOR2") (pin "8") (pinfunction "VDD_8") (pintype "power_in"))
      (node (ref "U2") (pin "17") (pinfunction "IO19_17") (pintype "bidirectional"))
    )
    (net (code "16") (name "INT_RTC") (class "Default")
      (node (ref "R1_PINH1") (pin "1") (pinfunction "1_1") (pintype "passive"))
      (node (ref "TP15") (pin "TP") (pinfunction "TP_TP") (pintype "input"))
      (node (ref "U2") (pin "8") (pinfunction "IO0_8") (pintype "bidirectional"))
      (node (ref "U3") (pin "3") (pinfunction "SQW/~{INT}_3") (pintype "output"))
    )
    (net (code "17") (name "IO{slash}BOOT") (class "Default")
      (node (ref "BOOT_BUTTON") (pin "3") (pinfunction "3_3") (pintype "passive"))
      (node (ref "BOOT_BUTTON") (pin "4") (pinfunction "4_4") (pintype "passive"))
      (node (ref "C6") (pin "1") (pinfunction "1_1") (pintype "passive"))
      (node (ref "R_BOOT") (pin "2") (pinfunction "2_2") (pintype "passive"))
      (node (ref "U2") (pin "15") (pinfunction "IO9_15") (pintype "bidirectional"))
    )
    (net (code "18") (name "IO{slash}CHANGE") (class "Default")
      (node (ref "C10") (pin "1") (pinfunction "1_1") (pintype "passive"))
      (node (ref "CHANGE_BUTTON") (pin "3") (pinfunction "3_3") (pintype "passive"))
      (node (ref "CHANGE_BUTTON") (pin "4") (pinfunction "4_4") (pintype "passive"))
      (node (ref "R_CHANGE") (pin "2") (pinfunction "2_2") (pintype "passive"))
      (node (ref "U2") (pin "23") (pinfunction "IO15_23") (pintype "bidirectional"))
    )
    (net (code "19") (name "MISO") (class "Default")
      (node (ref "D12") (pin "1") (pinfunction "1_1") (pintype "passive"))
      (node (ref "J4") (pin "P7") (pinfunction "DAT0_P7") (pintype "bidirectional"))
      (node (ref "R8") (pin "1") (pinfunction "1_1") (pintype "passive"))
      (node (ref "TP6") (pin "TP") (pinfunction "TP_TP") (pintype "input"))
      (node (ref "U1") (pin "2") (pinfunction "DO(IO1)_2") (pintype "bidirectional"))
      (node (ref "U2") (pin "27") (pinfunction "IO2_27") (pintype "bidirectional"))
    )
    (net (code "20") (name "MOSI") (class "Default")
      (node (ref "D11") (pin "1") (pinfunction "1_1") (pintype "passive"))
      (node (ref "J1") (pin "14") (pinfunction "14_14") (pintype "bidirectional"))
      (node (ref "J4") (pin "P3") (pinfunction "CMD_P3") (pintype "bidirectional"))
      (node (ref "R7") (pin "1") (pinfunction "1_1") (pintype "passive"))
      (node (ref "TP7") (pin "TP") (pinfunction "TP_TP") (pintype "input"))
      (node (ref "U1") (pin "5") (pinfunction "DI(IO0)_5") (pintype "bidirectional"))
      (node (ref "U2") (pin "7") (pinfunction "IO7_7") (pintype "bidirectional"))
    )
    (net (code "21") (name "Net-(CHG_LED-PadC)") (class "Default")
      (node (ref "CHG_LED") (pin "C") (pinfunction "C_C") (pintype "passive"))
      (node (ref "R1_BAT") (pin "1") (pinfunction "1_1") (pintype "passive"))
    )
    (net (code "22") (name "Net-(D2-CATHODE)") (class "Default")
      (node (ref "C1_BAT1") (pin "1") (pinfunction "1_1") (pintype "passive"))
      (node (ref "D2") (pin "1") (pinfunction "CATHODE_1") (pintype "bidirectional"))
      (node (ref "IC4") (pin "1") (pinfunction "VIN_1") (pintype "bidirectional"))
      (node (ref "IC4") (pin "3") (pinfunction "CE_3") (pintype "bidirectional"))
      (node (ref "Q1") (pin "2") (pinfunction "S_2") (pintype "bidirectional"))
    )
    (net (code "23") (name "Net-(D3-A)") (class "Default")
      (node (ref "C4") (pin "1") (pinfunction "1_1") (pintype "passive"))
      (node (ref "D3") (pin "2") (pinfunction "A_2") (pintype "bidirectional"))
      (node (ref "D4") (pin "1") (pinfunction "K_1") (pintype "bidirectional"))
    )
    (net (code "24") (name "Net-(D7-CATHODE)") (class "Default")
      (node (ref "D7") (pin "1") (pinfunction "CATHODE_1") (pintype "bidirectional"))
      (node (ref "R_CAPACITOR") (pin "1") (pinfunction "1_1") (pintype "passive"))
    )
    (net (code "25") (name "Net-(EPD_C1-Pad1)") (class "Default")
      (node (ref "EPD_C1") (pin "1") (pinfunction "1_1") (pintype "passive"))
      (node (ref "J1") (pin "4") (pinfunction "4_4") (pintype "bidirectional"))
    )
    (net (code "26") (name "Net-(EPD_C2-Pad1)") (class "Default")
      (node (ref "EPD_C2") (pin "1") (pinfunction "1_1") (pintype "passive"))
      (node (ref "J1") (pin "5") (pinfunction "5_5") (pintype "bidirectional"))
    )
    (net (code "27") (name "Net-(EPD_C6-Pad1)") (class "Default")
      (node (ref "EPD_C6") (pin "1") (pinfunction "1_1") (pintype "passive"))
      (node (ref "J1") (pin "18") (pinfunction "18_18") (pintype "bidirectional"))
    )
    (net (code "28") (name "Net-(EPD_C7-Pad1)") (class "Default")
      (node (ref "EPD_C7") (pin "1") (pinfunction "1_1") (pintype "passive"))
      (node (ref "J1") (pin "19") (pinfunction "19_19") (pintype "bidirectional"))
    )
    (net (code "29") (name "Net-(EPD_C8-Pad1)") (class "Default")
      (node (ref "EPD_C8") (pin "1") (pinfunction "1_1") (pintype "passive"))
      (node (ref "J1") (pin "20") (pinfunction "20_20") (pintype "bidirectional"))
    )
    (net (code "30") (name "Net-(EPD_C10-Pad1)") (class "Default")
      (node (ref "EPD_C10") (pin "1") (pinfunction "1_1") (pintype "passive"))
      (node (ref "J1") (pin "22") (pinfunction "22_22") (pintype "bidirectional"))
    )
    (net (code "31") (name "Net-(EPD_C12-Pad1)") (class "Default")
      (node (ref "EPD_C12") (pin "1") (pinfunction "1_1") (pintype "passive"))
      (node (ref "J1") (pin "24") (pinfunction "24_24") (pintype "bidirectional"))
    )
    (net (code "32") (name "Net-(IC1-CT)") (class "Default")
      (node (ref "C_DELAY") (pin "1") (pinfunction "1_1") (pintype "passive"))
      (node (ref "IC1") (pin "5") (pinfunction "CT_5") (pintype "bidirectional"))
    )
    (net (code "33") (name "Net-(J2-PadA5)") (class "Default")
      (node (ref "J2") (pin "A5") (pinfunction "A5_A5") (pintype "bidirectional"))
      (node (ref "R2-USB1") (pin "2") (pinfunction "2_2") (pintype "passive"))
    )
    (net (code "34") (name "Net-(J2-PadB5)") (class "Default")
      (node (ref "J2") (pin "B5") (pinfunction "B5_B5") (pintype "bidirectional"))
      (node (ref "R2-USB") (pin "1") (pinfunction "1_1") (pintype "passive"))
    )
    (net (code "35") (name "Net-(MCP73831-PROG)") (class "Default")
      (node (ref "MCP73831") (pin "5") (pinfunction "PROG_5") (pintype "input"))
      (node (ref "R2_BAT") (pin "2") (pinfunction "2_2") (pintype "passive"))
    )
    (net (code "36") (name "Net-(MCP73831-STAT)") (class "Default")
      (node (ref "MCP73831") (pin "1") (pinfunction "STAT_1") (pintype "output"))
      (node (ref "R1_BAT") (pin "2") (pinfunction "2_2") (pintype "passive"))
    )
    (net (code "37") (name "PREVGH") (class "Default")
      (node (ref "D5") (pin "1") (pinfunction "K_1") (pintype "bidirectional"))
      (node (ref "EPD_C9") (pin "1") (pinfunction "1_1") (pintype "passive"))
      (node (ref "J1") (pin "21") (pinfunction "21_21") (pintype "bidirectional"))
    )
    (net (code "38") (name "PREVGL") (class "Default")
      (node (ref "D4") (pin "2") (pinfunction "A_2") (pintype "bidirectional"))
      (node (ref "EPD_C11") (pin "1") (pinfunction "1_1") (pintype "passive"))
      (node (ref "J1") (pin "23") (pinfunction "23_23") (pintype "bidirectional"))
    )
    (net (code "39") (name "RESE") (class "Default")
      (node (ref "J1") (pin "3") (pinfunction "3_3") (pintype "bidirectional"))
      (node (ref "Q3") (pin "2") (pinfunction "S_2") (pintype "bidirectional"))
      (node (ref "R3") (pin "2") (pinfunction "2_2") (pintype "passive"))
    )
    (net (code "40") (name "RESE'") (class "Default")
      (node (ref "R2") (pin "2") (pinfunction "2_2") (pintype "passive"))
      (node (ref "R3") (pin "1") (pinfunction "1_1") (pintype "passive"))
      (node (ref "SJ1") (pin "2") (pinfunction "2_2") (pintype "passive"))
    )
    (net (code "41") (name "RESET") (class "Default")
      (node (ref "C5") (pin "1") (pinfunction "1_1") (pintype "passive"))
      (node (ref "IC1") (pin "1") (pinfunction "VOUT_1") (pintype "bidirectional"))
      (node (ref "RESET_BUTTON") (pin "3") (pinfunction "3_3") (pintype "passive"))
      (node (ref "RESET_BUTTON") (pin "4") (pinfunction "4_4") (pintype "passive"))
      (node (ref "R_RESET") (pin "2") (pinfunction "2_2") (pintype "passive"))
      (node (ref "U2") (pin "3") (pinfunction "EN_3") (pintype "input"))
    )
    (net (code "42") (name "RTC_RST") (class "Default")
      (node (ref "U2") (pin "16") (pinfunction "IO18_16") (pintype "bidirectional"))
      (node (ref "U3") (pin "4") (pinfunction "~{RST}_4") (pintype "input"))
    )
    (net (code "43") (name "RX") (class "Default")
      (node (ref "TP2") (pin "TP") (pinfunction "TP_TP") (pintype "input"))
      (node (ref "U2") (pin "24") (pinfunction "RXD0/GPIO17_24") (pintype "bidirectional"))
    )
    (net (code "44") (name "SCK") (class "Default")
      (node (ref "D10") (pin "1") (pinfunction "1_1") (pintype "passive"))
      (node (ref "J1") (pin "13") (pinfunction "13_13") (pintype "bidirectional"))
      (node (ref "J4") (pin "P5") (pinfunction "CLK_P5") (pintype "bidirectional"))
      (node (ref "R6") (pin "1") (pinfunction "1_1") (pintype "passive"))
      (node (ref "TP8") (pin "TP") (pinfunction "TP_TP") (pintype "input"))
      (node (ref "U1") (pin "6") (pinfunction "CLK_6") (pintype "input"))
      (node (ref "U2") (pin "6") (pinfunction "IO6_6") (pintype "bidirectional"))
    )
    (net (code "45") (name "SCL") (class "Default")
      (node (ref "J3") (pin "4") (pinfunction "4_4") (pintype "passive"))
      (node (ref "R2_PINH") (pin "1") (pinfunction "1_1") (pintype "passive"))
      (node (ref "SENSOR2") (pin "4") (pinfunction "SCK_4") (pintype "input"))
      (node (ref "U2") (pin "20") (pinfunction "IO22_20") (pintype "bidirectional"))
      (node (ref "U3") (pin "16") (pinfunction "SCL_16") (pintype "input"))
      (node (ref "U4") (pin "7") (pinfunction "SCL_7") (pintype "input"))
    )
    (net (code "46") (name "SDA") (class "Default")
      (node (ref "J3") (pin "3") (pinfunction "3_3") (pintype "passive"))
      (node (ref "R1_PINH") (pin "1") (pinfunction "1_1") (pintype "passive"))
      (node (ref "SENSOR2") (pin "3") (pinfunction "SDI_3") (pintype "bidirectional"))
      (node (ref "U2") (pin "19") (pinfunction "IO21_19") (pintype "bidirectional"))
      (node (ref "U3") (pin "15") (pinfunction "SDA_15") (pintype "bidirectional"))
      (node (ref "U4") (pin "8") (pinfunction "SDA_8") (pintype "bidirectional"))
    )
    (net (code "47") (name "SRC") (class "Default")
      (node (ref "C4") (pin "2") (pinfunction "2_2") (pintype "passive"))
      (node (ref "D5") (pin "2") (pinfunction "A_2") (pintype "bidirectional"))
      (node (ref "L1") (pin "1") (pinfunction "1_1") (pintype "passive"))
      (node (ref "Q3") (pin "3") (pinfunction "D_3") (pintype "bidirectional"))
    )
    (net (code "48") (name "SS_SD") (class "Default")
      (node (ref "D8") (pin "1") (pinfunction "1_1") (pintype "passive"))
      (node (ref "J4") (pin "P2") (pinfunction "CD/DAT3_P2") (pintype "bidirectional"))
      (node (ref "R10") (pin "1") (pinfunction "1_1") (pintype "passive"))
      (node (ref "U2") (pin "4") (pinfunction "IO4_4") (pintype "bidirectional"))
    )
    (net (code "49") (name "TX") (class "Default")
      (node (ref "TP1") (pin "TP") (pinfunction "TP_TP") (pintype "input"))
      (node (ref "U2") (pin "25") (pinfunction "TXD0/GPIO16_25") (pintype "bidirectional"))
    )
    (net (code "50") (name "USB_D+") (class "Default")
      (node (ref "D1") (pin "4") (pinfunction "I/O2_2_4") (pintype "bidirectional"))
      (node (ref "U2") (pin "14") (pinfunction "IO13_14") (pintype "bidirectional"))
    )
    (net (code "51") (name "USB_D-") (class "Default")
      (node (ref "D1") (pin "6") (pinfunction "I/O1_2_6") (pintype "bidirectional"))
      (node (ref "U2") (pin "13") (pinfunction "IO12_13") (pintype "bidirectional"))
    )
    (net (code "52") (name "VBAT") (class "Default")
      (node (ref "C2_BAT") (pin "1") (pinfunction "1_1") (pintype "passive"))
      (node (ref "MCP73831") (pin "3") (pinfunction "VBAT_3") (pintype "power_in"))
      (node (ref "Q1") (pin "3") (pinfunction "D_3") (pintype "bidirectional"))
      (node (ref "TP3") (pin "TP") (pinfunction "TP_TP") (pintype "input"))
      (node (ref "U4") (pin "2") (pinfunction "CELL_2") (pintype "power_in"))
      (node (ref "U4") (pin "3") (pinfunction "VDD_3") (pintype "power_in"))
    )
    (net (code "53") (name "VBUS") (class "Default")
      (node (ref "C1_BAT") (pin "1") (pinfunction "1_1") (pintype "passive"))
      (node (ref "C4_USB") (pin "1") (pinfunction "1_1") (pintype "passive"))
      (node (ref "C5_USB") (pin "1") (pinfunction "1_1") (pintype "passive"))
      (node (ref "CHG_LED") (pin "A") (pinfunction "A_A") (pintype "passive"))
      (node (ref "D1") (pin "2") (pinfunction "GND_2") (pintype "bidirectional"))
      (node (ref "D2") (pin "2") (pinfunction "ANODE_2") (pintype "bidirectional"))
      (node (ref "MCP73831") (pin "4") (pinfunction "VIN_4") (pintype "power_in"))
      (node (ref "PFMF.050.1") (pin "2") (pinfunction "2_2") (pintype "passive"))
      (node (ref "Q1") (pin "1") (pinfunction "G_1") (pintype "bidirectional"))
      (node (ref "R1_PWRUSB") (pin "1") (pinfunction "1_1") (pintype "passive"))
      (node (ref "TP14") (pin "TP") (pinfunction "TP_TP") (pintype "input"))
    )
    (net (code "54") (name "VRTC") (class "Default")
      (node (ref "C10_SUPERCAP") (pin "2") (pinfunction "2_2") (pintype "passive"))
      (node (ref "C8") (pin "1") (pinfunction "1_1") (pintype "passive"))
      (node (ref "R_CAPACITOR") (pin "2") (pinfunction "2_2") (pintype "passive"))
      (node (ref "U3") (pin "14") (pinfunction "VBAT_14") (pintype "power_in"))
    )
    (net (code "55") (name "VUSB") (class "Default")
      (node (ref "J2") (pin "A4") (pinfunction "A4_A4") (pintype "bidirectional"))
      (node (ref "J2") (pin "A9") (pinfunction "A9_A9") (pintype "bidirectional"))
      (node (ref "J2") (pin "B4") (pinfunction "B4_B4") (pintype "bidirectional"))
      (node (ref "J2") (pin "B9") (pinfunction "B9_B9") (pintype "bidirectional"))
      (node (ref "PFMF.050.1") (pin "1") (pinfunction "1_1") (pintype "passive"))
    )
    (net (code "56") (name "unconnected-(IC1-NC-Pad4)") (class "Default")
      (node (ref "IC1") (pin "4") (pinfunction "NC_4") (pintype "no_connect"))
    )
    (net (code "57") (name "unconnected-(IC4-NC-Pad4)") (class "Default")
      (node (ref "IC4") (pin "4") (pinfunction "NC_4") (pintype "no_connect"))
    )
    (net (code "58") (name "unconnected-(J1-Pad1)") (class "Default")
      (node (ref "J1") (pin "1") (pinfunction "1_1") (pintype "bidirectional"))
    )
    (net (code "59") (name "unconnected-(J1-Pad6)") (class "Default")
      (node (ref "J1") (pin "6") (pinfunction "6_6") (pintype "bidirectional"))
    )
    (net (code "60") (name "unconnected-(J1-Pad7)") (class "Default")
      (node (ref "J1") (pin "7") (pinfunction "7_7") (pintype "bidirectional"))
    )
    (net (code "61") (name "unconnected-(J2-PadA8)") (class "Default")
      (node (ref "J2") (pin "A8") (pinfunction "A8_A8") (pintype "bidirectional"))
    )
    (net (code "62") (name "unconnected-(J2-PadB8)") (class "Default")
      (node (ref "J2") (pin "B8") (pinfunction "B8_B8") (pintype "bidirectional"))
    )
    (net (code "63") (name "unconnected-(J4-DAT1-PadP8)") (class "Default")
      (node (ref "J4") (pin "P8") (pinfunction "DAT1_P8") (pintype "bidirectional"))
    )
    (net (code "64") (name "unconnected-(J4-DAT2-PadP1)") (class "Default")
      (node (ref "J4") (pin "P1") (pinfunction "DAT2_P1") (pintype "bidirectional"))
    )
    (net (code "65") (name "unconnected-(J4-DETECTION_1-PadS1)") (class "Default")
      (node (ref "J4") (pin "S1") (pinfunction "DETECTION_1_S1") (pintype "bidirectional"))
    )
    (net (code "66") (name "unconnected-(J4-DETECTION_2-PadS2)") (class "Default")
      (node (ref "J4") (pin "S2") (pinfunction "DETECTION_2_S2") (pintype "bidirectional"))
    )
    (net (code "67") (name "unconnected-(U2-NC-Pad22)") (class "Default")
      (node (ref "U2") (pin "22") (pinfunction "NC_22") (pintype "no_connect"))
    )
    (net (code "68") (name "unconnected-(U4-~{ALERT}-Pad5)") (class "Default")
      (node (ref "U4") (pin "5") (pinfunction "~{ALERT}_5") (pintype "output"))
    )
  )
)
